# pcb__2024-09-19.net
KiCad netlist of a schematic drawn in EasyEDA Pro
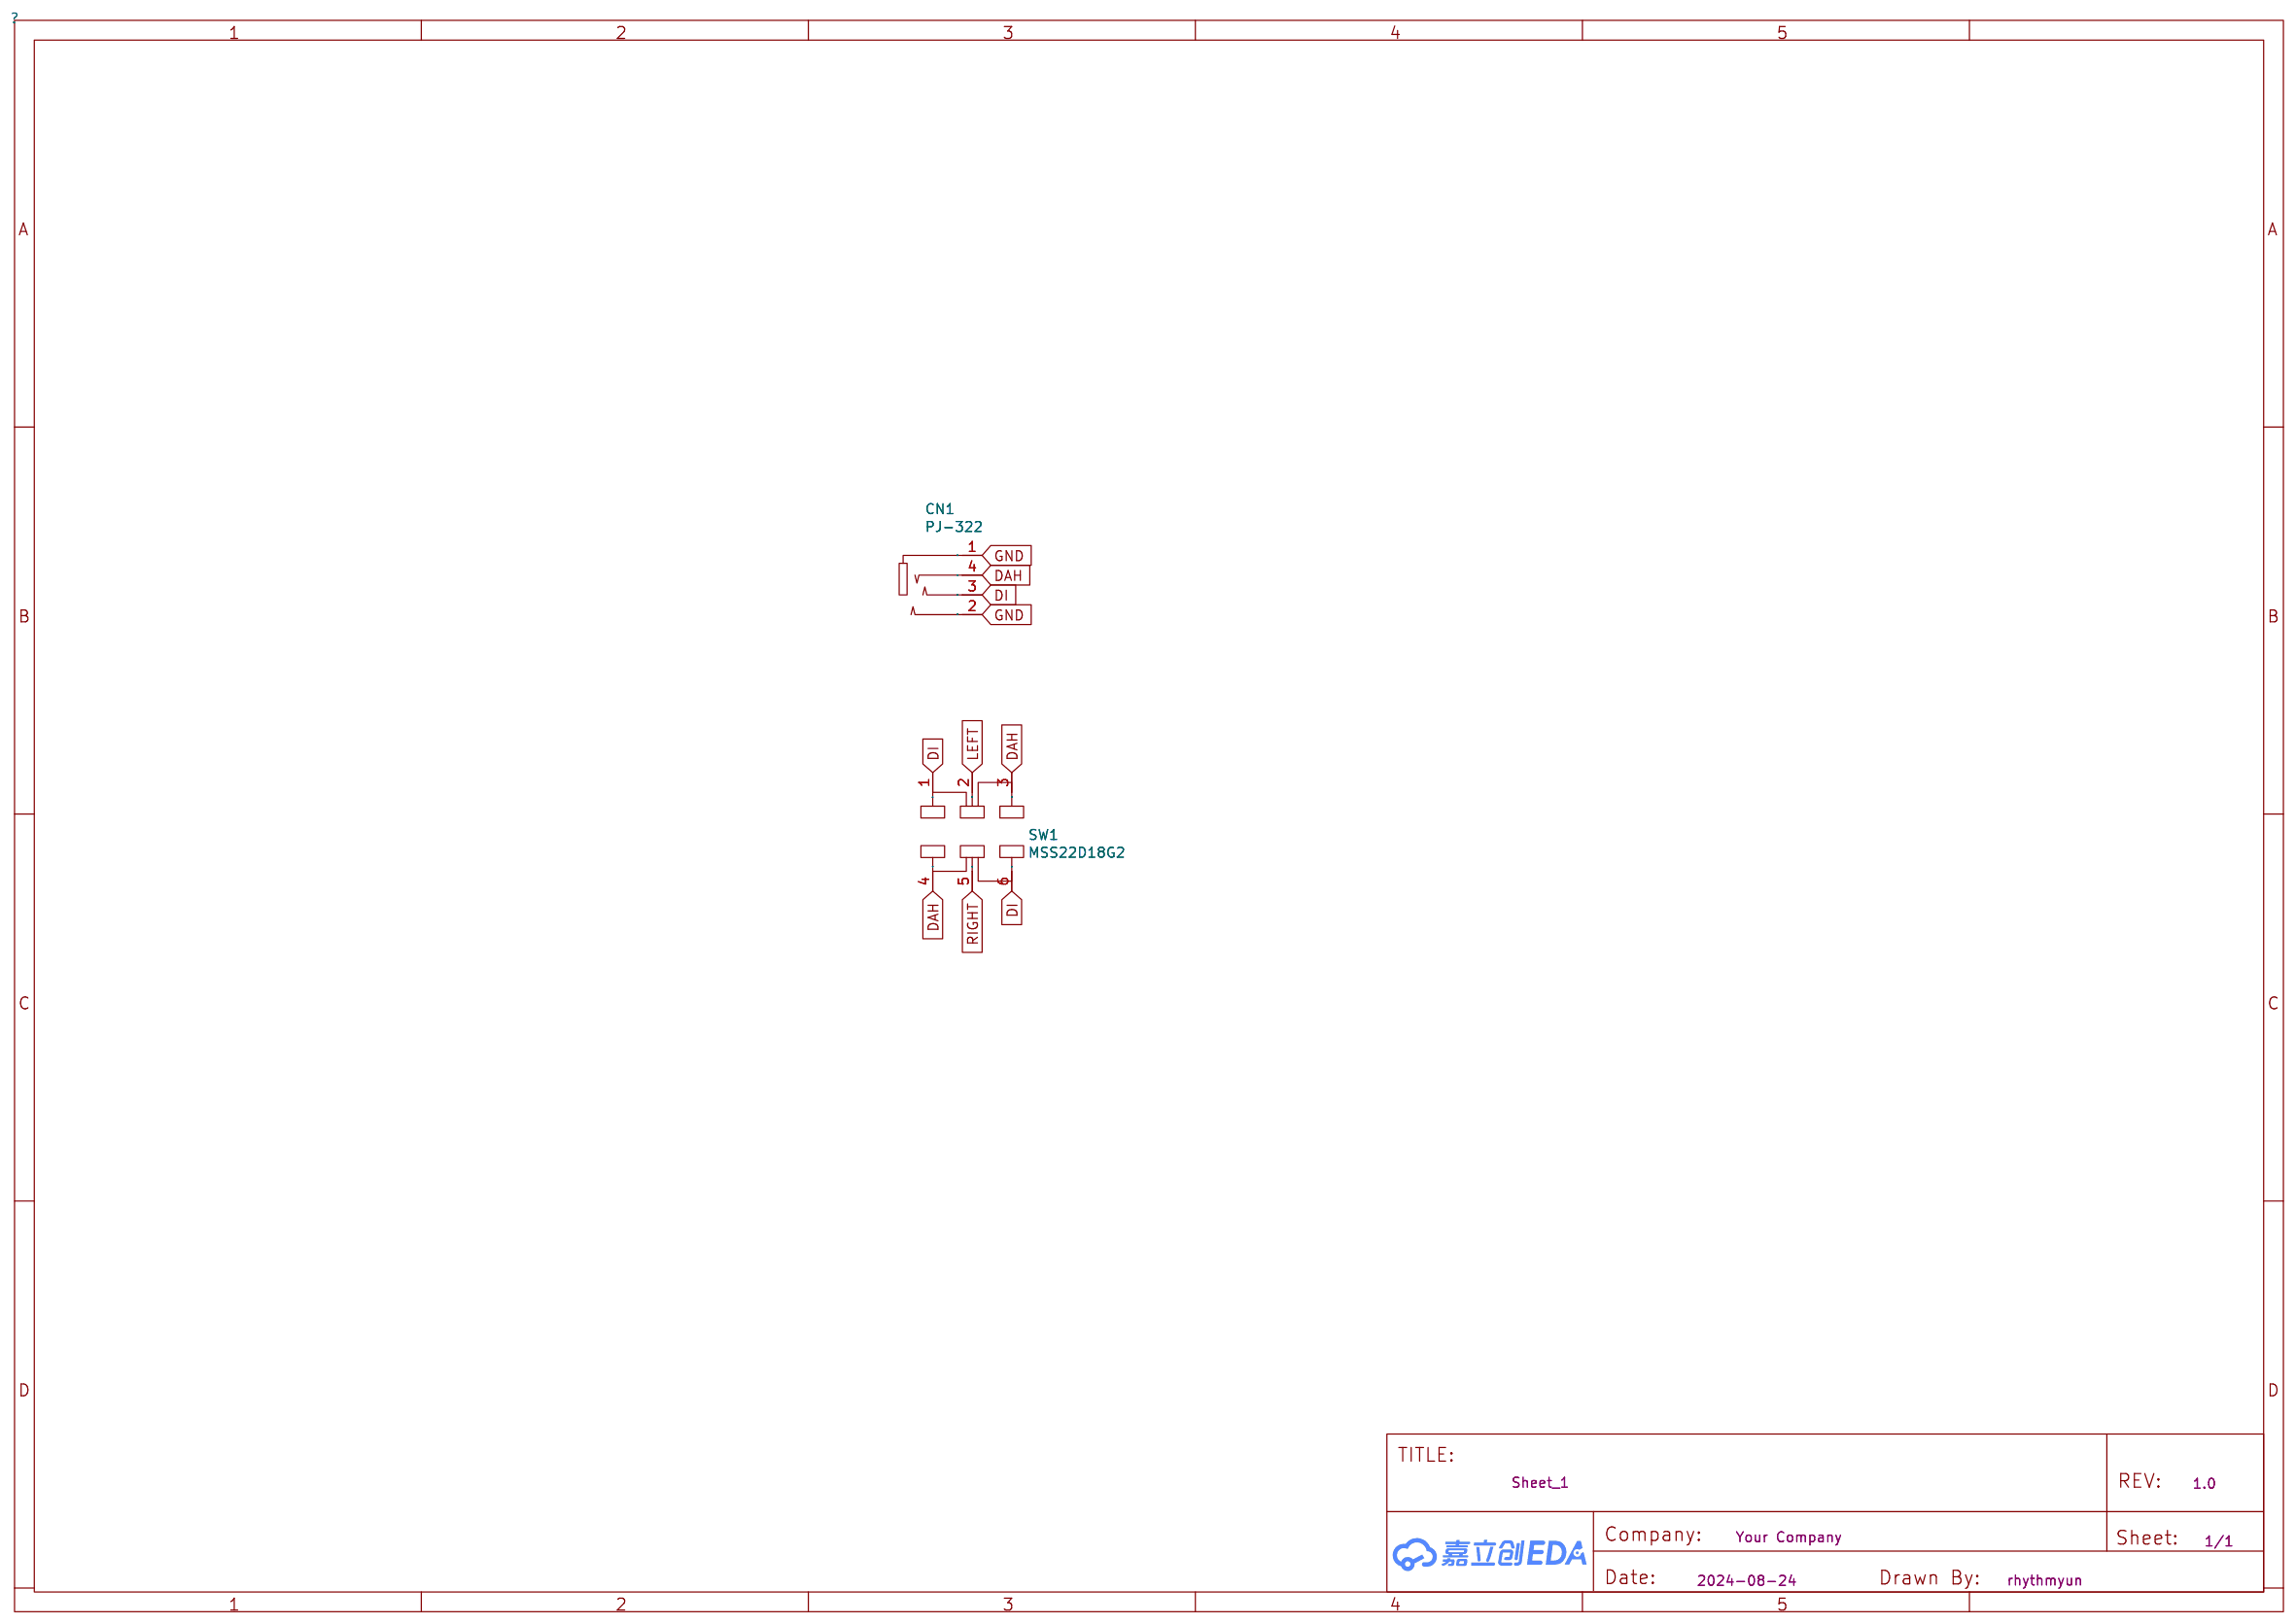
[diagram p0: schematic sheet]

(export (version "E")
  (design (tool "Eeschema 10.0.6"))
  (components
    (comp (ref "CN1")
      (value "PJ-322")
      (footprint "easyedapro:AUDIO-TH_HOOYA_PJ-322")
      (fields (field (name "Manufacturer Part") "PJ-322环保") (field (name "Manufacturer") "HOOYA(皓宇电子)"))
      (libsource (lib "easyedapro") (part "PJ-322"))
    )
    (comp (ref "SW1")
      (value "MSS22D18G2")
      (footprint "easyedapro:SW-TH_MSS22D18GX")
      (fields (field (name "Manufacturer") "SHOU HAN(首韩)"))
      (libsource (lib "easyedapro") (part "MSS22D18G2"))
    )
  )
  (nets
    (net (code "1") (name "DAH") (class "Default")
      (node (ref "CN1") (pin "4") (pinfunction "4_4") (pintype "unspecified"))
      (node (ref "SW1") (pin "3") (pinfunction "3_3") (pintype "unspecified"))
      (node (ref "SW1") (pin "4") (pinfunction "4_4") (pintype "unspecified"))
    )
    (net (code "2") (name "DI") (class "Default")
      (node (ref "CN1") (pin "3") (pinfunction "3_3") (pintype "unspecified"))
      (node (ref "SW1") (pin "1") (pinfunction "1_1") (pintype "unspecified"))
      (node (ref "SW1") (pin "6") (pinfunction "6_6") (pintype "unspecified"))
    )
    (net (code "3") (name "GND") (class "Default")
      (node (ref "CN1") (pin "1") (pinfunction "1_1") (pintype "unspecified"))
      (node (ref "CN1") (pin "2") (pinfunction "2_2") (pintype "unspecified"))
    )
    (net (code "4") (name "LEFT") (class "Default")
      (node (ref "SW1") (pin "2") (pinfunction "2_2") (pintype "unspecified"))
    )
    (net (code "5") (name "RIGHT") (class "Default")
      (node (ref "SW1") (pin "5") (pinfunction "5_5") (pintype "unspecified"))
    )
  )
)
